# MacroUzaz_Schematic.net
KiCad netlist of a schematic drawn in Altium Designer
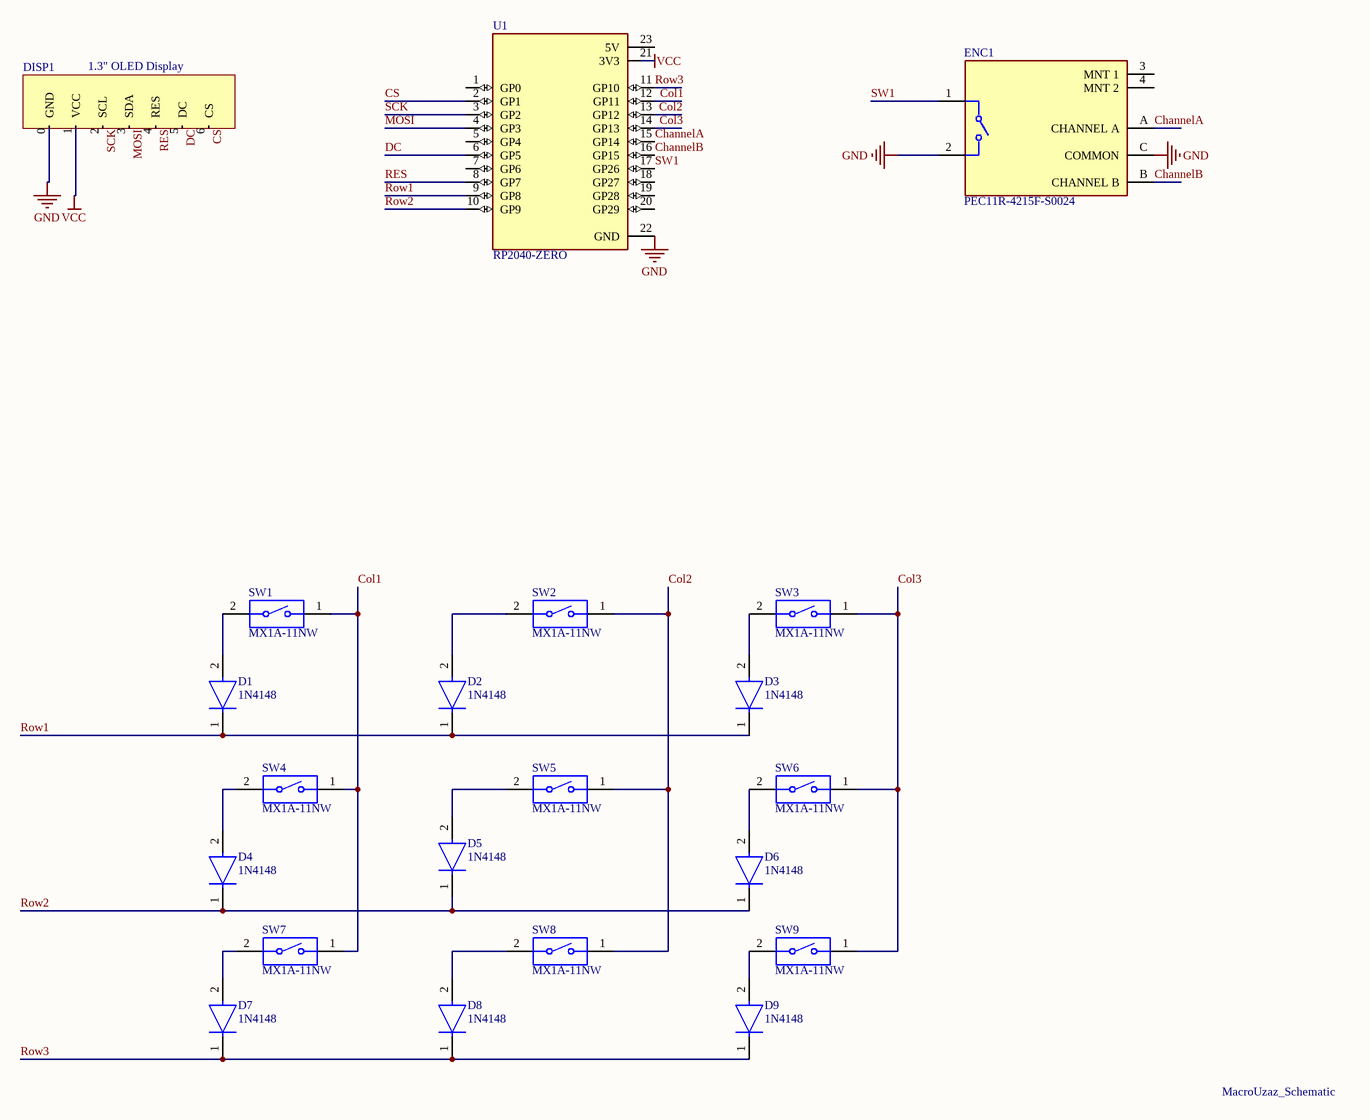
[diagram p0: MacroUzaz_Schematic.SchDoc]

(export (version "E")
  (design (tool "Eeschema 10.0.6"))
  (components
    (comp (ref "D1")
      (value "1N4148")
      (footprint "FP-017AG-MFG")
      (description "DIODE GEN PURP 100V 200MA DO35")
      (fields (field (name "VOLTAGE") "100V"))
      (libsource (lib "Altium Content Vault") (part "d7152d700b627762746794eb795d46e"))
    )
    (comp (ref "D2")
      (value "1N4148")
      (footprint "FP-017AG-MFG")
      (description "DIODE GEN PURP 100V 200MA DO35")
      (fields (field (name "VOLTAGE") "100V"))
      (libsource (lib "Altium Content Vault") (part "d7152d700b627762746794eb795d46e"))
    )
    (comp (ref "D3")
      (value "1N4148")
      (footprint "FP-017AG-MFG")
      (description "DIODE GEN PURP 100V 200MA DO35")
      (fields (field (name "VOLTAGE") "100V"))
      (libsource (lib "Altium Content Vault") (part "d7152d700b627762746794eb795d46e"))
    )
    (comp (ref "D4")
      (value "1N4148")
      (footprint "FP-017AG-MFG")
      (description "DIODE GEN PURP 100V 200MA DO35")
      (fields (field (name "VOLTAGE") "100V"))
      (libsource (lib "Altium Content Vault") (part "d7152d700b627762746794eb795d46e"))
    )
    (comp (ref "D5")
      (value "1N4148")
      (footprint "FP-017AG-MFG")
      (description "DIODE GEN PURP 100V 200MA DO35")
      (fields (field (name "VOLTAGE") "100V"))
      (libsource (lib "Altium Content Vault") (part "d7152d700b627762746794eb795d46e"))
    )
    (comp (ref "D6")
      (value "1N4148")
      (footprint "FP-017AG-MFG")
      (description "DIODE GEN PURP 100V 200MA DO35")
      (fields (field (name "VOLTAGE") "100V"))
      (libsource (lib "Altium Content Vault") (part "d7152d700b627762746794eb795d46e"))
    )
    (comp (ref "D7")
      (value "1N4148")
      (footprint "FP-017AG-MFG")
      (description "DIODE GEN PURP 100V 200MA DO35")
      (fields (field (name "VOLTAGE") "100V"))
      (libsource (lib "Altium Content Vault") (part "d7152d700b627762746794eb795d46e"))
    )
    (comp (ref "D8")
      (value "1N4148")
      (footprint "FP-017AG-MFG")
      (description "DIODE GEN PURP 100V 200MA DO35")
      (fields (field (name "VOLTAGE") "100V"))
      (libsource (lib "Altium Content Vault") (part "d7152d700b627762746794eb795d46e"))
    )
    (comp (ref "D9")
      (value "1N4148")
      (footprint "FP-017AG-MFG")
      (description "DIODE GEN PURP 100V 200MA DO35")
      (fields (field (name "VOLTAGE") "100V"))
      (libsource (lib "Altium Content Vault") (part "d7152d700b627762746794eb795d46e"))
    )
    (comp (ref "DISP1")
      (value "1.3\" OLED Display")
      (footprint "OLED_Display")
      (libsource (lib "Integrated_Library1") (part "OLED_Connector"))
    )
    (comp (ref "ENC1")
      (value "PEC11R-4215F-S0024")
      (footprint "FP-PEC11R-4215F-S0024-MFG")
      (description "ROTARY ENCODER MECHANICAL 24PPR")
      (libsource (lib "Altium Content Vault") (part "5f1dd25a4c49fa66e7eeb899730fe11"))
    )
    (comp (ref "SW1")
      (value "MX1A-11NW")
      (footprint "CHRY-MX1A-11NW_V")
      (description "Keylock Switch, 12 V, -10 to 70 degC, 2-Pin THD, RoHS, Bulk")
      (fields (field (name "MANUFACTURER") "Cherry") (field (name "PART NO") "MX1A11NW"))
      (libsource (lib "Altium Content Vault") (part "KEYSW-SPST-2"))
    )
    (comp (ref "SW2")
      (value "MX1A-11NW")
      (footprint "CHRY-MX1A-11NW_V")
      (description "Keylock Switch, 12 V, -10 to 70 degC, 2-Pin THD, RoHS, Bulk")
      (fields (field (name "MANUFACTURER") "Cherry") (field (name "PART NO") "MX1A11NW"))
      (libsource (lib "Altium Content Vault") (part "KEYSW-SPST-2"))
    )
    (comp (ref "SW3")
      (value "MX1A-11NW")
      (footprint "CHRY-MX1A-11NW_V")
      (description "Keylock Switch, 12 V, -10 to 70 degC, 2-Pin THD, RoHS, Bulk")
      (fields (field (name "MANUFACTURER") "Cherry") (field (name "PART NO") "MX1A11NW"))
      (libsource (lib "Altium Content Vault") (part "KEYSW-SPST-2"))
    )
    (comp (ref "SW4")
      (value "MX1A-11NW")
      (footprint "CHRY-MX1A-11NW_V")
      (description "Keylock Switch, 12 V, -10 to 70 degC, 2-Pin THD, RoHS, Bulk")
      (fields (field (name "MANUFACTURER") "Cherry") (field (name "PART NO") "MX1A11NW"))
      (libsource (lib "Altium Content Vault") (part "KEYSW-SPST-2"))
    )
    (comp (ref "SW5")
      (value "MX1A-11NW")
      (footprint "CHRY-MX1A-11NW_V")
      (description "Keylock Switch, 12 V, -10 to 70 degC, 2-Pin THD, RoHS, Bulk")
      (fields (field (name "MANUFACTURER") "Cherry") (field (name "PART NO") "MX1A11NW"))
      (libsource (lib "Altium Content Vault") (part "KEYSW-SPST-2"))
    )
    (comp (ref "SW6")
      (value "MX1A-11NW")
      (footprint "CHRY-MX1A-11NW_V")
      (description "Keylock Switch, 12 V, -10 to 70 degC, 2-Pin THD, RoHS, Bulk")
      (fields (field (name "MANUFACTURER") "Cherry") (field (name "PART NO") "MX1A11NW"))
      (libsource (lib "Altium Content Vault") (part "KEYSW-SPST-2"))
    )
    (comp (ref "SW7")
      (value "MX1A-11NW")
      (footprint "CHRY-MX1A-11NW_V")
      (description "Keylock Switch, 12 V, -10 to 70 degC, 2-Pin THD, RoHS, Bulk")
      (fields (field (name "MANUFACTURER") "Cherry") (field (name "PART NO") "MX1A11NW"))
      (libsource (lib "Altium Content Vault") (part "KEYSW-SPST-2"))
    )
    (comp (ref "SW8")
      (value "MX1A-11NW")
      (footprint "CHRY-MX1A-11NW_V")
      (description "Keylock Switch, 12 V, -10 to 70 degC, 2-Pin THD, RoHS, Bulk")
      (fields (field (name "MANUFACTURER") "Cherry") (field (name "PART NO") "MX1A11NW"))
      (libsource (lib "Altium Content Vault") (part "KEYSW-SPST-2"))
    )
    (comp (ref "SW9")
      (value "MX1A-11NW")
      (footprint "CHRY-MX1A-11NW_V")
      (description "Keylock Switch, 12 V, -10 to 70 degC, 2-Pin THD, RoHS, Bulk")
      (fields (field (name "MANUFACTURER") "Cherry") (field (name "PART NO") "MX1A11NW"))
      (libsource (lib "Altium Content Vault") (part "KEYSW-SPST-2"))
    )
    (comp (ref "U1")
      (value "RP2040-ZERO")
      (footprint "MODULE_RP2040-ZERO")
      (description "Low-Cost, High-Performance Pico-Like MCU Board Based On Raspberry Pi Microcontroller RP2040")
      (fields (field (name "MF") "Waveshare Electronics"))
      (libsource (lib "Syed Uzair Ali") (part "RP2040-ZERO"))
    )
  )
  (nets
    (net (code "1") (name "/CS") (class "Default")
      (node (ref "DISP1") (pin "6") (pinfunction "CS_6") (pintype "input"))
      (node (ref "U1") (pin "2") (pinfunction "GP1_2") (pintype "bidirectional"))
    )
    (net (code "2") (name "/ChannelA") (class "Default")
      (node (ref "ENC1") (pin "A") (pinfunction "CHANNEL_A_A") (pintype "passive"))
      (node (ref "U1") (pin "15") (pinfunction "GP14_15") (pintype "bidirectional"))
    )
    (net (code "3") (name "/ChannelB") (class "Default")
      (node (ref "ENC1") (pin "B") (pinfunction "CHANNEL_B_B") (pintype "passive"))
      (node (ref "U1") (pin "16") (pinfunction "GP15_16") (pintype "bidirectional"))
    )
    (net (code "4") (name "/Col1") (class "Default")
      (node (ref "SW1") (pin "1") (pinfunction "1_1") (pintype "passive"))
      (node (ref "SW4") (pin "1") (pinfunction "1_1") (pintype "passive"))
      (node (ref "SW7") (pin "1") (pinfunction "1_1") (pintype "passive"))
      (node (ref "U1") (pin "12") (pinfunction "GP11_12") (pintype "bidirectional"))
    )
    (net (code "5") (name "/Col2") (class "Default")
      (node (ref "SW2") (pin "1") (pinfunction "1_1") (pintype "passive"))
      (node (ref "SW5") (pin "1") (pinfunction "1_1") (pintype "passive"))
      (node (ref "SW8") (pin "1") (pinfunction "1_1") (pintype "passive"))
      (node (ref "U1") (pin "13") (pinfunction "GP12_13") (pintype "bidirectional"))
    )
    (net (code "6") (name "/Col3") (class "Default")
      (node (ref "SW3") (pin "1") (pinfunction "1_1") (pintype "passive"))
      (node (ref "SW6") (pin "1") (pinfunction "1_1") (pintype "passive"))
      (node (ref "SW9") (pin "1") (pinfunction "1_1") (pintype "passive"))
      (node (ref "U1") (pin "14") (pinfunction "GP13_14") (pintype "bidirectional"))
    )
    (net (code "7") (name "/DC") (class "Default")
      (node (ref "DISP1") (pin "5") (pinfunction "DC_5") (pintype "input"))
      (node (ref "U1") (pin "6") (pinfunction "GP5_6") (pintype "bidirectional"))
    )
    (net (code "8") (name "/MOSI") (class "Default")
      (node (ref "DISP1") (pin "3") (pinfunction "SDA_3") (pintype "input"))
      (node (ref "U1") (pin "4") (pinfunction "GP3_4") (pintype "bidirectional"))
    )
    (net (code "9") (name "/RES") (class "Default")
      (node (ref "DISP1") (pin "4") (pinfunction "RES_4") (pintype "input"))
      (node (ref "U1") (pin "8") (pinfunction "GP7_8") (pintype "bidirectional"))
    )
    (net (code "10") (name "/Row1") (class "Default")
      (node (ref "D1") (pin "1") (pinfunction "C_1") (pintype "passive"))
      (node (ref "D2") (pin "1") (pinfunction "C_1") (pintype "passive"))
      (node (ref "D3") (pin "1") (pinfunction "C_1") (pintype "passive"))
      (node (ref "U1") (pin "9") (pinfunction "GP8_9") (pintype "bidirectional"))
    )
    (net (code "11") (name "/Row2") (class "Default")
      (node (ref "D4") (pin "1") (pinfunction "C_1") (pintype "passive"))
      (node (ref "D5") (pin "1") (pinfunction "C_1") (pintype "passive"))
      (node (ref "D6") (pin "1") (pinfunction "C_1") (pintype "passive"))
      (node (ref "U1") (pin "10") (pinfunction "GP9_10") (pintype "bidirectional"))
    )
    (net (code "12") (name "/Row3") (class "Default")
      (node (ref "D7") (pin "1") (pinfunction "C_1") (pintype "passive"))
      (node (ref "D8") (pin "1") (pinfunction "C_1") (pintype "passive"))
      (node (ref "D9") (pin "1") (pinfunction "C_1") (pintype "passive"))
      (node (ref "U1") (pin "11") (pinfunction "GP10_11") (pintype "bidirectional"))
    )
    (net (code "13") (name "/SCK") (class "Default")
      (node (ref "DISP1") (pin "2") (pinfunction "SCL_2") (pintype "input"))
      (node (ref "U1") (pin "3") (pinfunction "GP2_3") (pintype "bidirectional"))
    )
    (net (code "14") (name "/SW1") (class "Default")
      (node (ref "ENC1") (pin "1") (pinfunction "1_1") (pintype "passive"))
      (node (ref "U1") (pin "17") (pinfunction "GP26_17") (pintype "bidirectional"))
    )
    (net (code "15") (name "GND") (class "Default")
      (node (ref "DISP1") (pin "0") (pinfunction "GND_0") (pintype "power_in"))
      (node (ref "ENC1") (pin "2") (pinfunction "2_2") (pintype "passive"))
      (node (ref "ENC1") (pin "C") (pinfunction "COMMON_C") (pintype "passive"))
      (node (ref "U1") (pin "22") (pinfunction "GND_22") (pintype "power_in"))
    )
    (net (code "16") (name "Net-(D1-A)") (class "Default")
      (node (ref "D1") (pin "2") (pinfunction "A_2") (pintype "passive"))
      (node (ref "SW1") (pin "2") (pinfunction "2_2") (pintype "passive"))
    )
    (net (code "17") (name "Net-(D2-A)") (class "Default")
      (node (ref "D2") (pin "2") (pinfunction "A_2") (pintype "passive"))
      (node (ref "SW2") (pin "2") (pinfunction "2_2") (pintype "passive"))
    )
    (net (code "18") (name "Net-(D3-A)") (class "Default")
      (node (ref "D3") (pin "2") (pinfunction "A_2") (pintype "passive"))
      (node (ref "SW3") (pin "2") (pinfunction "2_2") (pintype "passive"))
    )
    (net (code "19") (name "Net-(D4-A)") (class "Default")
      (node (ref "D4") (pin "2") (pinfunction "A_2") (pintype "passive"))
      (node (ref "SW4") (pin "2") (pinfunction "2_2") (pintype "passive"))
    )
    (net (code "20") (name "Net-(D5-A)") (class "Default")
      (node (ref "D5") (pin "2") (pinfunction "A_2") (pintype "passive"))
      (node (ref "SW5") (pin "2") (pinfunction "2_2") (pintype "passive"))
    )
    (net (code "21") (name "Net-(D6-A)") (class "Default")
      (node (ref "D6") (pin "2") (pinfunction "A_2") (pintype "passive"))
      (node (ref "SW6") (pin "2") (pinfunction "2_2") (pintype "passive"))
    )
    (net (code "22") (name "Net-(D7-A)") (class "Default")
      (node (ref "D7") (pin "2") (pinfunction "A_2") (pintype "passive"))
      (node (ref "SW7") (pin "2") (pinfunction "2_2") (pintype "passive"))
    )
    (net (code "23") (name "Net-(D8-A)") (class "Default")
      (node (ref "D8") (pin "2") (pinfunction "A_2") (pintype "passive"))
      (node (ref "SW8") (pin "2") (pinfunction "2_2") (pintype "passive"))
    )
    (net (code "24") (name "Net-(D9-A)") (class "Default")
      (node (ref "D9") (pin "2") (pinfunction "A_2") (pintype "passive"))
      (node (ref "SW9") (pin "2") (pinfunction "2_2") (pintype "passive"))
    )
    (net (code "25") (name "VCC") (class "Default")
      (node (ref "DISP1") (pin "1") (pinfunction "VCC_1") (pintype "power_in"))
      (node (ref "U1") (pin "21") (pinfunction "3V3_21") (pintype "power_in"))
    )
    (net (code "26") (name "unconnected-(ENC1-MNT_1-Pad3)") (class "Default")
      (node (ref "ENC1") (pin "3") (pinfunction "MNT_1_3") (pintype "passive"))
    )
    (net (code "27") (name "unconnected-(ENC1-MNT_2-Pad4)") (class "Default")
      (node (ref "ENC1") (pin "4") (pinfunction "MNT_2_4") (pintype "passive"))
    )
    (net (code "28") (name "unconnected-(U1-5V-Pad23)") (class "Default")
      (node (ref "U1") (pin "23") (pinfunction "5V_23") (pintype "power_in"))
    )
    (net (code "29") (name "unconnected-(U1-GP0-Pad1)") (class "Default")
      (node (ref "U1") (pin "1") (pinfunction "GP0_1") (pintype "bidirectional"))
    )
    (net (code "30") (name "unconnected-(U1-GP4-Pad5)") (class "Default")
      (node (ref "U1") (pin "5") (pinfunction "GP4_5") (pintype "bidirectional"))
    )
    (net (code "31") (name "unconnected-(U1-GP6-Pad7)") (class "Default")
      (node (ref "U1") (pin "7") (pinfunction "GP6_7") (pintype "bidirectional"))
    )
    (net (code "32") (name "unconnected-(U1-GP27-Pad18)") (class "Default")
      (node (ref "U1") (pin "18") (pinfunction "GP27_18") (pintype "bidirectional"))
    )
    (net (code "33") (name "unconnected-(U1-GP28-Pad19)") (class "Default")
      (node (ref "U1") (pin "19") (pinfunction "GP28_19") (pintype "bidirectional"))
    )
    (net (code "34") (name "unconnected-(U1-GP29-Pad20)") (class "Default")
      (node (ref "U1") (pin "20") (pinfunction "GP29_20") (pintype "bidirectional"))
    )
  )
)
